# compact.net
KiCad netlist of a schematic drawn in EAGLE
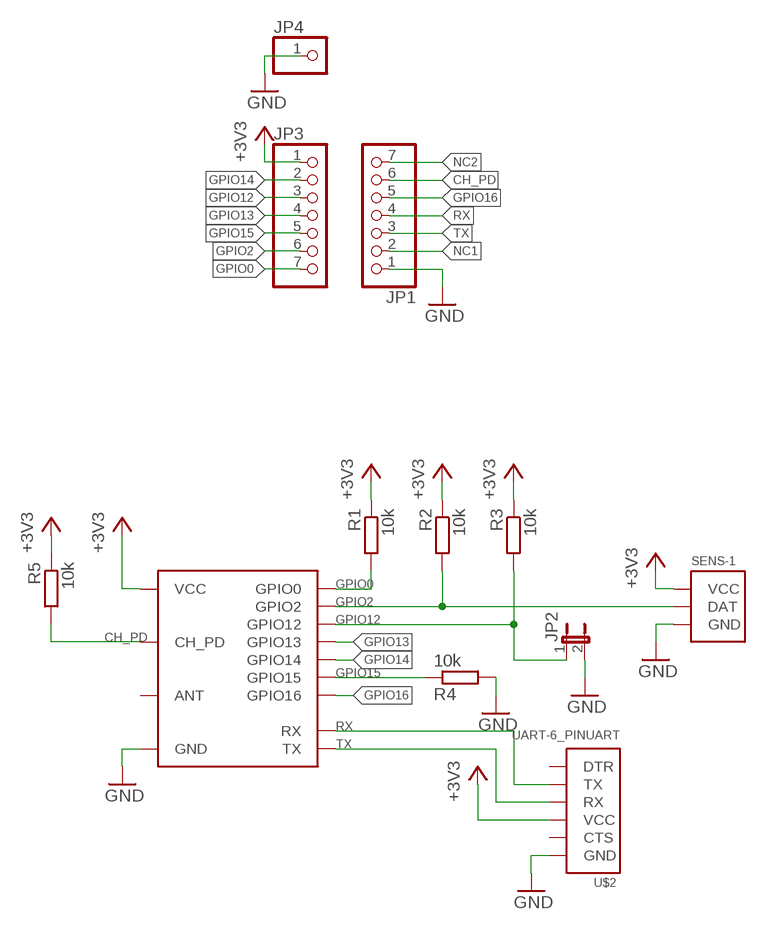
[diagram p0: schematic, sheet 1]

(export (version "E")
  (design (tool "Eeschema 10.0.6"))
  (components
    (comp (ref "JP1")
      (value "PINHD-1X7")
      (footprint "eagle-import:1X07")
      (libsource (lib "eagle-import") (part "PINHD-1X7"))
    )
    (comp (ref "JP2")
      (value "JP1E")
      (footprint "eagle-import:JP1")
      (libsource (lib "eagle-import") (part "JP1E"))
    )
    (comp (ref "JP3")
      (value "PINHD-1X7")
      (footprint "eagle-import:1X07")
      (libsource (lib "eagle-import") (part "PINHD-1X7"))
    )
    (comp (ref "JP4")
      (value "PINHD-1X1")
      (footprint "eagle-import:1X01")
      (libsource (lib "eagle-import") (part "PINHD-1X1"))
    )
    (comp (ref "R1")
      (value "10k")
      (footprint "eagle-import:R0603")
      (libsource (lib "eagle-import") (part "R-EU_R0603"))
    )
    (comp (ref "R2")
      (value "10k")
      (footprint "eagle-import:R0603")
      (libsource (lib "eagle-import") (part "R-EU_R0603"))
    )
    (comp (ref "R3")
      (value "10k")
      (footprint "eagle-import:R0603")
      (libsource (lib "eagle-import") (part "R-EU_R0603"))
    )
    (comp (ref "R4")
      (value "10k")
      (footprint "eagle-import:R0603")
      (libsource (lib "eagle-import") (part "R-EU_R0603"))
    )
    (comp (ref "R5")
      (value "10k")
      (footprint "eagle-import:R0603")
      (libsource (lib "eagle-import") (part "R-EU_R0603"))
    )
    (comp (ref "SENS-1")
      (value "DHT11DHT11")
      (footprint "eagle-import:SENSOR-DHT11")
      (libsource (lib "eagle-import") (part "DHT11DHT11"))
    )
    (comp (ref "U$1")
      (value "ESP8266-03")
      (footprint "eagle-import:ESP8266-ESP-03")
      (libsource (lib "eagle-import") (part "ESP8266-03"))
    )
    (comp (ref "U$2")
      (value "UART-6_PINUART")
      (footprint "eagle-import:ANGLE-1X6")
      (libsource (lib "eagle-import") (part "UART-6_PINUART"))
    )
  )
  (nets
    (net (code "1") (name "+3V3") (class "Default")
      (node (ref "JP3") (pin "1") (pinfunction "1_1") (pintype "passive"))
      (node (ref "R1") (pin "1") (pinfunction "1_1") (pintype "passive"))
      (node (ref "R2") (pin "1") (pinfunction "1_1") (pintype "passive"))
      (node (ref "R3") (pin "1") (pinfunction "1_1") (pintype "passive"))
      (node (ref "R5") (pin "1") (pinfunction "1_1") (pintype "passive"))
      (node (ref "SENS-1") (pin "P$1") (pinfunction "VCC_P$1") (pintype "bidirectional"))
      (node (ref "U$1") (pin "P$8") (pinfunction "VCC_P$8") (pintype "bidirectional"))
      (node (ref "U$2") (pin "3") (pinfunction "VCC_3") (pintype "bidirectional"))
    )
    (net (code "2") (name "CH_PD") (class "Default")
      (node (ref "JP1") (pin "6") (pinfunction "6_6") (pintype "passive"))
      (node (ref "R5") (pin "2") (pinfunction "2_2") (pintype "passive"))
      (node (ref "U$1") (pin "P$6") (pinfunction "CH_PD_P$6") (pintype "bidirectional"))
    )
    (net (code "3") (name "GND") (class "Default")
      (node (ref "JP1") (pin "1") (pinfunction "1_1") (pintype "passive"))
      (node (ref "JP2") (pin "2") (pinfunction "2_2") (pintype "passive"))
      (node (ref "JP4") (pin "1") (pinfunction "1_1") (pintype "passive"))
      (node (ref "R4") (pin "2") (pinfunction "2_2") (pintype "passive"))
      (node (ref "SENS-1") (pin "P$4") (pinfunction "GND_P$4") (pintype "bidirectional"))
      (node (ref "U$1") (pin "P$1") (pinfunction "GND_P$1") (pintype "bidirectional"))
      (node (ref "U$2") (pin "1") (pinfunction "GND_1") (pintype "bidirectional"))
    )
    (net (code "4") (name "GPIO0") (class "Default")
      (node (ref "JP3") (pin "7") (pinfunction "7_7") (pintype "passive"))
      (node (ref "R1") (pin "2") (pinfunction "2_2") (pintype "passive"))
      (node (ref "U$1") (pin "P$14") (pinfunction "GPIO0_P$14") (pintype "bidirectional"))
    )
    (net (code "5") (name "GPIO2") (class "Default")
      (node (ref "JP3") (pin "6") (pinfunction "6_6") (pintype "passive"))
      (node (ref "R2") (pin "2") (pinfunction "2_2") (pintype "passive"))
      (node (ref "SENS-1") (pin "P$2") (pinfunction "DAT_P$2") (pintype "bidirectional"))
      (node (ref "U$1") (pin "P$13") (pinfunction "GPIO2_P$13") (pintype "bidirectional"))
    )
    (net (code "6") (name "GPIO12") (class "Default")
      (node (ref "JP2") (pin "1") (pinfunction "1_1") (pintype "passive"))
      (node (ref "JP3") (pin "3") (pinfunction "3_3") (pintype "passive"))
      (node (ref "R3") (pin "2") (pinfunction "2_2") (pintype "passive"))
      (node (ref "U$1") (pin "P$10") (pinfunction "GPIO12_P$10") (pintype "bidirectional"))
    )
    (net (code "7") (name "GPIO13") (class "Default")
      (node (ref "JP3") (pin "4") (pinfunction "4_4") (pintype "passive"))
      (node (ref "U$1") (pin "P$11") (pinfunction "GPIO13_P$11") (pintype "bidirectional"))
    )
    (net (code "8") (name "GPIO14") (class "Default")
      (node (ref "JP3") (pin "2") (pinfunction "2_2") (pintype "passive"))
      (node (ref "U$1") (pin "P$9") (pinfunction "GPIO14_P$9") (pintype "bidirectional"))
    )
    (net (code "9") (name "GPIO15") (class "Default")
      (node (ref "JP3") (pin "5") (pinfunction "5_5") (pintype "passive"))
      (node (ref "R4") (pin "1") (pinfunction "1_1") (pintype "passive"))
      (node (ref "U$1") (pin "P$12") (pinfunction "GPIO15_P$12") (pintype "bidirectional"))
    )
    (net (code "10") (name "GPIO16") (class "Default")
      (node (ref "JP1") (pin "5") (pinfunction "5_5") (pintype "passive"))
      (node (ref "U$1") (pin "P$5") (pinfunction "GPIO16_P$5") (pintype "bidirectional"))
    )
    (net (code "11") (name "NC1") (class "Default")
      (node (ref "JP1") (pin "2") (pinfunction "2_2") (pintype "passive"))
    )
    (net (code "12") (name "NC2") (class "Default")
      (node (ref "JP1") (pin "7") (pinfunction "7_7") (pintype "passive"))
    )
    (net (code "13") (name "RX") (class "Default")
      (node (ref "JP1") (pin "4") (pinfunction "4_4") (pintype "passive"))
      (node (ref "U$1") (pin "P$4") (pinfunction "RX_P$4") (pintype "bidirectional"))
      (node (ref "U$2") (pin "5") (pinfunction "TX_5") (pintype "bidirectional"))
    )
    (net (code "14") (name "TX") (class "Default")
      (node (ref "JP1") (pin "3") (pinfunction "3_3") (pintype "passive"))
      (node (ref "U$1") (pin "P$3") (pinfunction "TX_P$3") (pintype "bidirectional"))
      (node (ref "U$2") (pin "4") (pinfunction "RX_4") (pintype "bidirectional"))
    )
    (net (code "15") (name "unconnected-(U$1-ANT-PadP$7)") (class "Default")
      (node (ref "U$1") (pin "P$7") (pinfunction "ANT_P$7") (pintype "bidirectional"))
    )
    (net (code "16") (name "unconnected-(U$2-CTS-Pad2)") (class "Default")
      (node (ref "U$2") (pin "2") (pinfunction "CTS_2") (pintype "bidirectional"))
    )
    (net (code "17") (name "unconnected-(U$2-DTR-Pad6)") (class "Default")
      (node (ref "U$2") (pin "6") (pinfunction "DTR_6") (pintype "bidirectional"))
    )
  )
)
